# sd-card.net
KiCad netlist of a schematic drawn in Altium Designer
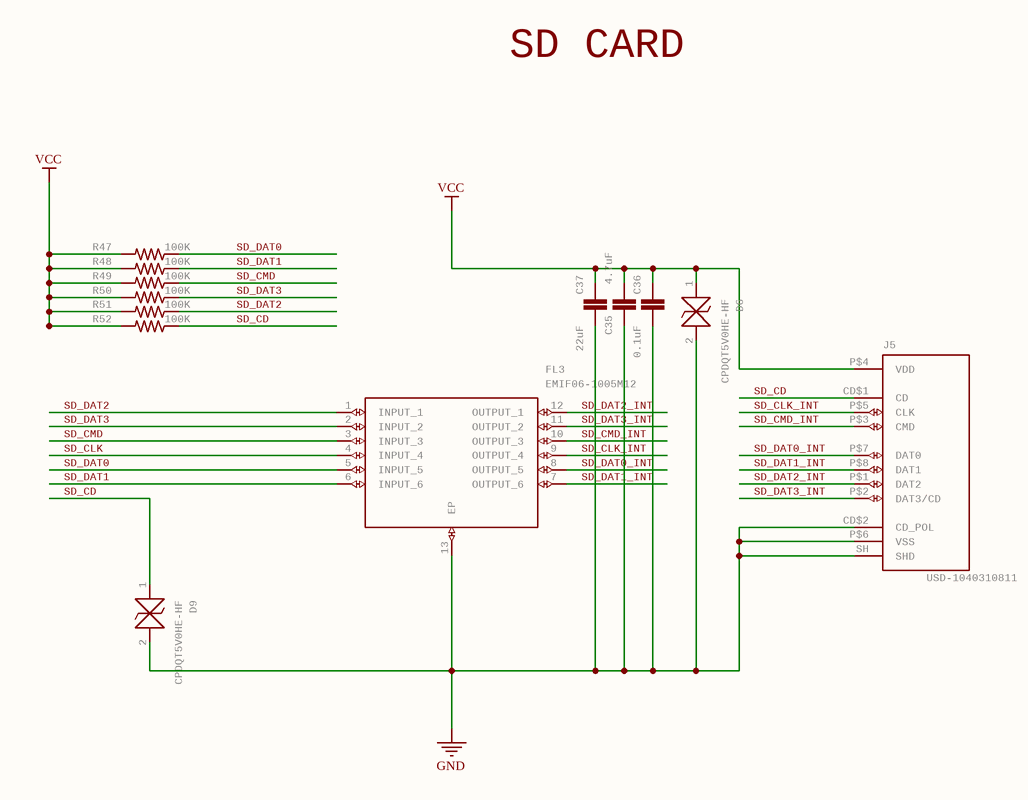
[diagram p0: sd-card.SchDoc]

(export (version "E")
  (design (tool "Eeschema 10.0.6"))
  (components
    (comp (ref "C35")
      (value "4.7uF")
      (footprint "0402-CAP")
      (description "CapacitorStandard 0603 ceramic capacitor, and 0.1\" leaded capacitor.")
      (fields (field (name "MPN") "JMK105BBJ475MV-F"))
      (libsource (lib "rt10") (part "CAP0402-CAP"))
    )
    (comp (ref "C36")
      (value "0.1uF")
      (footprint "0402-CAP")
      (description "CAPACITOR, European symbol")
      (fields (field (name "MPN") "C0402C104Z4VAC"))
      (libsource (lib "rt10") (part "C-EUC0201"))
    )
    (comp (ref "C37")
      (value "22uF")
      (footprint "0805")
      (fields (field (name "MPN") "CL21A226MQQNNNE"))
      (libsource (lib "rt10") (part "22UF-0805-6.3V-20%"))
    )
    (comp (ref "D6")
      (value "CPDQT5V0HE-HF")
      (footprint "CPDQT5V0HEHF")
      (description "ESD Suppressors / TVS Diodes DIODE ESD 5VWM 65W 0402/SOD-923F   Source:  Datasheet")
      (fields (field (name "MOUSER_PART_NUMBER") "MOUSER_PART_NUMBER"))
      (libsource (lib "rt10") (part "CPDQT5V0HE-HF"))
    )
    (comp (ref "D9")
      (value "CPDQT5V0HE-HF")
      (footprint "CPDQT5V0HEHF")
      (description "ESD Suppressors / TVS Diodes DIODE ESD 5VWM 65W 0402/SOD-923F   Source:  Datasheet")
      (fields (field (name "MOUSER_PART_NUMBER") "MOUSER_PART_NUMBER"))
      (libsource (lib "rt10") (part "CPDQT5V0HE-HF"))
    )
    (comp (ref "FL3")
      (value "EMIF06-1005M12")
      (footprint "SON40P150X250X65-13N")
      (description "EMI Filter Circuits 6lin lw cpcitnc EMI 45pF -35db @ 900MHz   Source:  Datasheet")
      (fields (field (name "MOUSER_PART_NUMBER") "511-EMIF06-1005M12"))
      (libsource (lib "rt10") (part "EMIF06-1005M12"))
    )
    (comp (ref "J5")
      (value "USD-1040310811")
      (footprint "1040310811")
      (description "uSD Slot")
      (fields (field (name "MPN") "104031-0811"))
      (libsource (lib "rt10") (part "USD-1040310811"))
    )
    (comp (ref "R47")
      (value "100K")
      (footprint "0402-RES")
      (description "ResistorBasic schematic elements and footprints for 0603, 1206, and PTH resistors.")
      (fields (field (name "MPN") "AC0402FR-07100KL"))
      (libsource (lib "rt10") (part "RESISTOR0402-RES"))
    )
    (comp (ref "R48")
      (value "100K")
      (footprint "0402-RES")
      (description "ResistorBasic schematic elements and footprints for 0603, 1206, and PTH resistors.")
      (fields (field (name "MPN") "AC0402FR-07100KL"))
      (libsource (lib "rt10") (part "RESISTOR0402-RES"))
    )
    (comp (ref "R49")
      (value "100K")
      (footprint "0402-RES")
      (description "ResistorBasic schematic elements and footprints for 0603, 1206, and PTH resistors.")
      (fields (field (name "MPN") "AC0402FR-07100KL"))
      (libsource (lib "rt10") (part "RESISTOR0402-RES"))
    )
    (comp (ref "R50")
      (value "100K")
      (footprint "0402-RES")
      (description "ResistorBasic schematic elements and footprints for 0603, 1206, and PTH resistors.")
      (fields (field (name "MPN") "AC0402FR-07100KL"))
      (libsource (lib "rt10") (part "RESISTOR0402-RES"))
    )
    (comp (ref "R51")
      (value "100K")
      (footprint "0402-RES")
      (description "ResistorBasic schematic elements and footprints for 0603, 1206, and PTH resistors.")
      (fields (field (name "MPN") "AC0402FR-07100KL"))
      (libsource (lib "rt10") (part "RESISTOR0402-RES"))
    )
    (comp (ref "R52")
      (value "100K")
      (footprint "0402-RES")
      (description "ResistorBasic schematic elements and footprints for 0603, 1206, and PTH resistors.")
      (fields (field (name "MPN") "AC0402FR-07100KL"))
      (libsource (lib "rt10") (part "RESISTOR0402-RES"))
    )
  )
  (nets
    (net (code "1") (name "/SD_CD") (class "Default")
      (node (ref "D9") (pin "1") (pinfunction "1_1") (pintype "bidirectional"))
      (node (ref "J5") (pin "CD$1") (pinfunction "CD_CD$1") (pintype "power_in"))
      (node (ref "R52") (pin "1") (pinfunction "1_1") (pintype "passive"))
    )
    (net (code "2") (name "/SD_CLK") (class "Default")
      (node (ref "FL3") (pin "4") (pinfunction "INPUT_4_4") (pintype "bidirectional"))
    )
    (net (code "3") (name "/SD_CLK_INT") (class "Default")
      (node (ref "FL3") (pin "9") (pinfunction "OUTPUT_4_9") (pintype "bidirectional"))
      (node (ref "J5") (pin "P$5") (pinfunction "CLK_P$5") (pintype "bidirectional"))
    )
    (net (code "4") (name "/SD_CMD") (class "Default")
      (node (ref "FL3") (pin "3") (pinfunction "INPUT_3_3") (pintype "bidirectional"))
      (node (ref "R49") (pin "1") (pinfunction "1_1") (pintype "passive"))
    )
    (net (code "5") (name "/SD_CMD_INT") (class "Default")
      (node (ref "FL3") (pin "10") (pinfunction "OUTPUT_3_10") (pintype "bidirectional"))
      (node (ref "J5") (pin "P$3") (pinfunction "CMD_P$3") (pintype "bidirectional"))
    )
    (net (code "6") (name "/SD_DAT0") (class "Default")
      (node (ref "FL3") (pin "5") (pinfunction "INPUT_5_5") (pintype "bidirectional"))
      (node (ref "R47") (pin "1") (pinfunction "1_1") (pintype "passive"))
    )
    (net (code "7") (name "/SD_DAT0_INT") (class "Default")
      (node (ref "FL3") (pin "8") (pinfunction "OUTPUT_5_8") (pintype "bidirectional"))
      (node (ref "J5") (pin "P$7") (pinfunction "DAT0_P$7") (pintype "bidirectional"))
    )
    (net (code "8") (name "/SD_DAT1") (class "Default")
      (node (ref "FL3") (pin "6") (pinfunction "INPUT_6_6") (pintype "bidirectional"))
      (node (ref "R48") (pin "1") (pinfunction "1_1") (pintype "passive"))
    )
    (net (code "9") (name "/SD_DAT1_INT") (class "Default")
      (node (ref "FL3") (pin "7") (pinfunction "OUTPUT_6_7") (pintype "bidirectional"))
      (node (ref "J5") (pin "P$8") (pinfunction "DAT1_P$8") (pintype "bidirectional"))
    )
    (net (code "10") (name "/SD_DAT2") (class "Default")
      (node (ref "FL3") (pin "1") (pinfunction "INPUT_1_1") (pintype "bidirectional"))
      (node (ref "R51") (pin "1") (pinfunction "1_1") (pintype "passive"))
    )
    (net (code "11") (name "/SD_DAT2_INT") (class "Default")
      (node (ref "FL3") (pin "12") (pinfunction "OUTPUT_1_12") (pintype "bidirectional"))
      (node (ref "J5") (pin "P$1") (pinfunction "DAT2_P$1") (pintype "bidirectional"))
    )
    (net (code "12") (name "/SD_DAT3") (class "Default")
      (node (ref "FL3") (pin "2") (pinfunction "INPUT_2_2") (pintype "bidirectional"))
      (node (ref "R50") (pin "1") (pinfunction "1_1") (pintype "passive"))
    )
    (net (code "13") (name "/SD_DAT3_INT") (class "Default")
      (node (ref "FL3") (pin "11") (pinfunction "OUTPUT_2_11") (pintype "bidirectional"))
      (node (ref "J5") (pin "P$2") (pinfunction "DAT3/CD_P$2") (pintype "bidirectional"))
    )
    (net (code "14") (name "GND") (class "Default")
      (node (ref "C35") (pin "1") (pinfunction "1_1") (pintype "passive"))
      (node (ref "C36") (pin "2") (pinfunction "2_2") (pintype "passive"))
      (node (ref "C37") (pin "2") (pinfunction "2_2") (pintype "passive"))
      (node (ref "D6") (pin "2") (pinfunction "2_2") (pintype "bidirectional"))
      (node (ref "D9") (pin "2") (pinfunction "2_2") (pintype "bidirectional"))
      (node (ref "FL3") (pin "13") (pinfunction "EP_13") (pintype "bidirectional"))
      (node (ref "J5") (pin "CD$2") (pinfunction "CD_POL_CD$2") (pintype "power_in"))
      (node (ref "J5") (pin "P$6") (pinfunction "VSS_P$6") (pintype "power_in"))
      (node (ref "J5") (pin "SH") (pinfunction "SHD_SH") (pintype "power_in"))
    )
    (net (code "15") (name "VCC") (class "Default")
      (node (ref "C35") (pin "2") (pinfunction "2_2") (pintype "passive"))
      (node (ref "C36") (pin "1") (pinfunction "1_1") (pintype "passive"))
      (node (ref "C37") (pin "1") (pinfunction "1_1") (pintype "passive"))
      (node (ref "D6") (pin "1") (pinfunction "1_1") (pintype "bidirectional"))
      (node (ref "J5") (pin "P$4") (pinfunction "VDD_P$4") (pintype "power_in"))
      (node (ref "R47") (pin "2") (pinfunction "2_2") (pintype "passive"))
      (node (ref "R48") (pin "2") (pinfunction "2_2") (pintype "passive"))
      (node (ref "R49") (pin "2") (pinfunction "2_2") (pintype "passive"))
      (node (ref "R50") (pin "2") (pinfunction "2_2") (pintype "passive"))
      (node (ref "R51") (pin "2") (pinfunction "2_2") (pintype "passive"))
      (node (ref "R52") (pin "2") (pinfunction "2_2") (pintype "passive"))
    )
  )
)
